# LED_Controller.net
KiCad netlist of a schematic drawn in Altium Designer
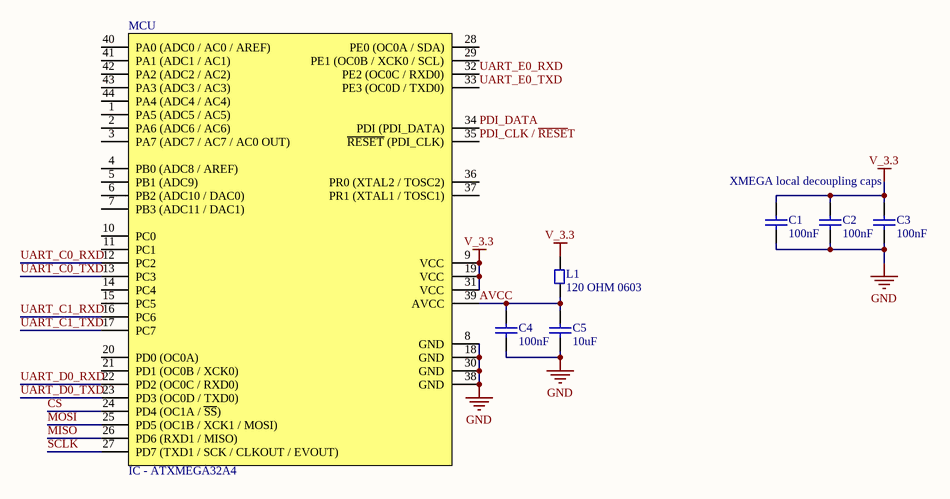
[diagram p0: LED_Controller.SchDoc]

(export (version "E")
  (design (tool "Eeschema 10.0.6"))
  (components
    (comp (ref "C1")
      (value "100nF")
      (footprint "0603")
      (description "CAP CER .10UF 50V X5R 0603")
      (fields
        (field (name "MANUFACTURER") "AVX Corporation")
        (field (name "MANUFACTURER PART NUMBER") "06035D104KAT2A")
      )
      (libsource (lib "My Schematic Library") (part "CP - 100nF 0603"))
    )
    (comp (ref "C2")
      (value "100nF")
      (footprint "0603")
      (description "CAP CER .10UF 50V X5R 0603")
      (fields
        (field (name "MANUFACTURER") "AVX Corporation")
        (field (name "MANUFACTURER PART NUMBER") "06035D104KAT2A")
      )
      (libsource (lib "My Schematic Library") (part "CP - 100nF 0603"))
    )
    (comp (ref "C3")
      (value "100nF")
      (footprint "0603")
      (description "CAP CER .10UF 50V X5R 0603")
      (fields
        (field (name "MANUFACTURER") "AVX Corporation")
        (field (name "MANUFACTURER PART NUMBER") "06035D104KAT2A")
      )
      (libsource (lib "My Schematic Library") (part "CP - 100nF 0603"))
    )
    (comp (ref "C4")
      (value "100nF")
      (footprint "0603")
      (description "CAP CER .10UF 50V X5R 0603")
      (fields
        (field (name "MANUFACTURER") "AVX Corporation")
        (field (name "MANUFACTURER PART NUMBER") "06035D104KAT2A")
      )
      (libsource (lib "My Schematic Library") (part "CP - 100nF 0603"))
    )
    (comp (ref "C5")
      (value "10uF")
      (footprint "0603")
      (description "CAP CER 10000PF 50V X7R 0603")
      (fields
        (field (name "MANUFACTURER") "TDK Corporation")
        (field (name "MANUFACTURER PART NUMBER") "C1608X7R1H103M")
      )
      (libsource (lib "My Schematic Library") (part "CP - 10uF 0603"))
    )
    (comp (ref "L1")
      (value "120 OHM 0603")
      (footprint "0603")
      (description "FERRITE BEAD 120 OHM 0603")
      (fields
        (field (name "MANUFACTURER") "Taiyo Yuden")
        (field (name "MANUFACTURER PART NUMBER") "FBMH1608HL121-T")
      )
      (libsource (lib "My Schematic Library") (part "L - Ferrite Bead 120 Ohm 0603"))
    )
    (comp (ref "MCU")
      (value "IC - ATXMEGA32A4")
      (footprint "QFN50P700X700X100-44N")
      (description "MCU AVR 32K FLASH 1.6V 44-QFN")
      (fields
        (field (name "MANUFACTURER") "Atmel")
        (field (name "MANUFACTURER PART NUMBER") "ATXMEGA32A4-MH")
      )
      (libsource (lib "My Schematic Library") (part "IC - ATXMEGA32A4"))
    )
  )
  (nets
    (net (code "1") (name "/AVCC") (class "Default")
      (node (ref "C4") (pin "2") (pintype "passive"))
      (node (ref "C5") (pin "2") (pintype "passive"))
      (node (ref "L1") (pin "1") (pintype "passive"))
      (node (ref "MCU") (pin "39") (pinfunction "AVCC_39") (pintype "passive"))
    )
    (net (code "2") (name "/CS") (class "Default")
      (node (ref "MCU") (pin "24") (pinfunction "PD4_(OC1A_/_~{SS})_24") (pintype "passive"))
    )
    (net (code "3") (name "/MISO") (class "Default")
      (node (ref "MCU") (pin "26") (pinfunction "PD6_(RXD1_/_MISO)_26") (pintype "passive"))
    )
    (net (code "4") (name "/MOSI") (class "Default")
      (node (ref "MCU") (pin "25") (pinfunction "PD5_(OC1B_/_XCK1_/_MOSI)_25") (pintype "passive"))
    )
    (net (code "5") (name "/PDI_CLK {slash} ~{RESE}T") (class "Default")
      (node (ref "MCU") (pin "35") (pinfunction "~{RESET}_(PDI_CLK)_35") (pintype "passive"))
    )
    (net (code "6") (name "/PDI_DATA") (class "Default")
      (node (ref "MCU") (pin "34") (pinfunction "PDI_(PDI_DATA)_34") (pintype "passive"))
    )
    (net (code "7") (name "/SCLK") (class "Default")
      (node (ref "MCU") (pin "27") (pinfunction "PD7_(TXD1_/_SCK_/_CLKOUT_/_EVOUT)_27") (pintype "passive"))
    )
    (net (code "8") (name "/UART_C0_RXD") (class "Default")
      (node (ref "MCU") (pin "12") (pinfunction "PC2_12") (pintype "passive"))
    )
    (net (code "9") (name "/UART_C0_TXD") (class "Default")
      (node (ref "MCU") (pin "13") (pinfunction "PC3_13") (pintype "passive"))
    )
    (net (code "10") (name "/UART_C1_RXD") (class "Default")
      (node (ref "MCU") (pin "16") (pinfunction "PC6_16") (pintype "passive"))
    )
    (net (code "11") (name "/UART_C1_TXD") (class "Default")
      (node (ref "MCU") (pin "17") (pinfunction "PC7_17") (pintype "passive"))
    )
    (net (code "12") (name "/UART_D0_RXD") (class "Default")
      (node (ref "MCU") (pin "22") (pinfunction "PD2_(OC0C_/_RXD0)_22") (pintype "passive"))
    )
    (net (code "13") (name "/UART_D0_TXD") (class "Default")
      (node (ref "MCU") (pin "23") (pinfunction "PD3_(OC0D_/_TXD0)_23") (pintype "passive"))
    )
    (net (code "14") (name "/UART_E0_RXD") (class "Default")
      (node (ref "MCU") (pin "32") (pinfunction "PE2_(OC0C_/_RXD0)_32") (pintype "passive"))
    )
    (net (code "15") (name "/UART_E0_TXD") (class "Default")
      (node (ref "MCU") (pin "33") (pinfunction "PE3_(OC0D_/_TXD0)_33") (pintype "passive"))
    )
    (net (code "16") (name "GND") (class "Default")
      (node (ref "C1") (pin "1") (pintype "passive"))
      (node (ref "C2") (pin "1") (pintype "passive"))
      (node (ref "C3") (pin "1") (pintype "passive"))
      (node (ref "C4") (pin "1") (pintype "passive"))
      (node (ref "C5") (pin "1") (pintype "passive"))
      (node (ref "MCU") (pin "18") (pinfunction "GND_18") (pintype "passive"))
      (node (ref "MCU") (pin "30") (pinfunction "GND_30") (pintype "passive"))
      (node (ref "MCU") (pin "38") (pinfunction "GND_38") (pintype "passive"))
      (node (ref "MCU") (pin "8") (pinfunction "GND_8") (pintype "passive"))
    )
    (net (code "17") (name "V_3.3") (class "Default")
      (node (ref "C1") (pin "2") (pintype "passive"))
      (node (ref "C2") (pin "2") (pintype "passive"))
      (node (ref "C3") (pin "2") (pintype "passive"))
      (node (ref "L1") (pin "2") (pintype "passive"))
      (node (ref "MCU") (pin "19") (pinfunction "VCC_19") (pintype "passive"))
      (node (ref "MCU") (pin "31") (pinfunction "VCC_31") (pintype "passive"))
      (node (ref "MCU") (pin "9") (pinfunction "VCC_9") (pintype "passive"))
    )
    (net (code "18") (name "unconnected-(MCU-PA0_(ADC0_{slash}_AC0_{slash}_AREF)-Pad40)") (class "Default")
      (node (ref "MCU") (pin "40") (pinfunction "PA0_(ADC0_/_AC0_/_AREF)_40") (pintype "passive"))
    )
    (net (code "19") (name "unconnected-(MCU-PA1_(ADC1_{slash}_AC1)-Pad41)") (class "Default")
      (node (ref "MCU") (pin "41") (pinfunction "PA1_(ADC1_/_AC1)_41") (pintype "passive"))
    )
    (net (code "20") (name "unconnected-(MCU-PA2_(ADC2_{slash}_AC2)-Pad42)") (class "Default")
      (node (ref "MCU") (pin "42") (pinfunction "PA2_(ADC2_/_AC2)_42") (pintype "passive"))
    )
    (net (code "21") (name "unconnected-(MCU-PA3_(ADC3_{slash}_AC3)-Pad43)") (class "Default")
      (node (ref "MCU") (pin "43") (pinfunction "PA3_(ADC3_/_AC3)_43") (pintype "passive"))
    )
    (net (code "22") (name "unconnected-(MCU-PA4_(ADC4_{slash}_AC4)-Pad44)") (class "Default")
      (node (ref "MCU") (pin "44") (pinfunction "PA4_(ADC4_/_AC4)_44") (pintype "passive"))
    )
    (net (code "23") (name "unconnected-(MCU-PA5_(ADC5_{slash}_AC5)-Pad1)") (class "Default")
      (node (ref "MCU") (pin "1") (pinfunction "PA5_(ADC5_/_AC5)_1") (pintype "passive"))
    )
    (net (code "24") (name "unconnected-(MCU-PA6_(ADC6_{slash}_AC6)-Pad2)") (class "Default")
      (node (ref "MCU") (pin "2") (pinfunction "PA6_(ADC6_/_AC6)_2") (pintype "passive"))
    )
    (net (code "25") (name "unconnected-(MCU-PA7_(ADC7_{slash}_AC7_{slash}_AC0_OUT)-Pad3)") (class "Default")
      (node (ref "MCU") (pin "3") (pinfunction "PA7_(ADC7_/_AC7_/_AC0_OUT)_3") (pintype "passive"))
    )
    (net (code "26") (name "unconnected-(MCU-PB0_(ADC8_{slash}_AREF)-Pad4)") (class "Default")
      (node (ref "MCU") (pin "4") (pinfunction "PB0_(ADC8_/_AREF)_4") (pintype "passive"))
    )
    (net (code "27") (name "unconnected-(MCU-PB1_(ADC9)-Pad5)") (class "Default")
      (node (ref "MCU") (pin "5") (pinfunction "PB1_(ADC9)_5") (pintype "passive"))
    )
    (net (code "28") (name "unconnected-(MCU-PB2_(ADC10_{slash}_DAC0)-Pad6)") (class "Default")
      (node (ref "MCU") (pin "6") (pinfunction "PB2_(ADC10_/_DAC0)_6") (pintype "passive"))
    )
    (net (code "29") (name "unconnected-(MCU-PB3_(ADC11_{slash}_DAC1)-Pad7)") (class "Default")
      (node (ref "MCU") (pin "7") (pinfunction "PB3_(ADC11_/_DAC1)_7") (pintype "passive"))
    )
    (net (code "30") (name "unconnected-(MCU-PC0-Pad10)") (class "Default")
      (node (ref "MCU") (pin "10") (pinfunction "PC0_10") (pintype "passive"))
    )
    (net (code "31") (name "unconnected-(MCU-PC1-Pad11)") (class "Default")
      (node (ref "MCU") (pin "11") (pinfunction "PC1_11") (pintype "passive"))
    )
    (net (code "32") (name "unconnected-(MCU-PC4-Pad14)") (class "Default")
      (node (ref "MCU") (pin "14") (pinfunction "PC4_14") (pintype "passive"))
    )
    (net (code "33") (name "unconnected-(MCU-PC5-Pad15)") (class "Default")
      (node (ref "MCU") (pin "15") (pinfunction "PC5_15") (pintype "passive"))
    )
    (net (code "34") (name "unconnected-(MCU-PD0_(OC0A)-Pad20)") (class "Default")
      (node (ref "MCU") (pin "20") (pinfunction "PD0_(OC0A)_20") (pintype "passive"))
    )
    (net (code "35") (name "unconnected-(MCU-PD1_(OC0B_{slash}_XCK0)-Pad21)") (class "Default")
      (node (ref "MCU") (pin "21") (pinfunction "PD1_(OC0B_/_XCK0)_21") (pintype "passive"))
    )
    (net (code "36") (name "unconnected-(MCU-PE0_(OC0A_{slash}_SDA)-Pad28)") (class "Default")
      (node (ref "MCU") (pin "28") (pinfunction "PE0_(OC0A_/_SDA)_28") (pintype "passive"))
    )
    (net (code "37") (name "unconnected-(MCU-PE1_(OC0B_{slash}_XCK0_{slash}_SCL)-Pad29)") (class "Default")
      (node (ref "MCU") (pin "29") (pinfunction "PE1_(OC0B_/_XCK0_/_SCL)_29") (pintype "passive"))
    )
    (net (code "38") (name "unconnected-(MCU-PR0_(XTAL2_{slash}_TOSC2)-Pad36)") (class "Default")
      (node (ref "MCU") (pin "36") (pinfunction "PR0_(XTAL2_/_TOSC2)_36") (pintype "passive"))
    )
    (net (code "39") (name "unconnected-(MCU-PR1_(XTAL1_{slash}_TOSC1)-Pad37)") (class "Default")
      (node (ref "MCU") (pin "37") (pinfunction "PR1_(XTAL1_/_TOSC1)_37") (pintype "passive"))
    )
  )
)
